# Reverse_current.net
KiCad netlist of a schematic drawn in EAGLE
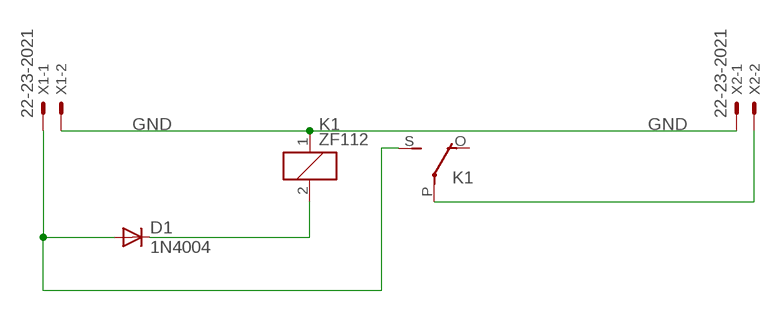
[diagram p0: schematic, sheet 1]

(export (version "E")
  (design (tool "Eeschema 10.0.6"))
  (components
    (comp (ref "D1")
      (value "1N4004")
      (footprint "eagle-import:DO41-10")
      (libsource (lib "eagle-import") (part "1N4004"))
    )
    (comp (ref "K1")
      (value "ZF112")
      (footprint "eagle-import:ZF112")
      (libsource (lib "eagle-import") (part "ZF112"))
    )
    (comp (ref "X1")
      (value "22-23-2021")
      (footprint "eagle-import:22-23-2021")
      (fields (field (name "MF") "MOLEX"))
      (libsource (lib "eagle-import") (part "22-23-2021"))
    )
    (comp (ref "X2")
      (value "22-23-2021")
      (footprint "eagle-import:22-23-2021")
      (fields (field (name "MF") "MOLEX"))
      (libsource (lib "eagle-import") (part "22-23-2021"))
    )
  )
  (nets
    (net (code "1") (name "/GND") (class "Default")
      (node (ref "K1") (pin "1") (pinfunction "1_1") (pintype "passive"))
      (node (ref "X1") (pin "2") (pinfunction "S_2") (pintype "passive"))
      (node (ref "X2") (pin "1") (pinfunction "S_1") (pintype "passive"))
    )
    (net (code "2") (name "Net-(D1-PadC)") (class "Default")
      (node (ref "D1") (pin "C") (pinfunction "C_C") (pintype "passive"))
      (node (ref "K1") (pin "2") (pinfunction "2_2") (pintype "passive"))
    )
    (net (code "3") (name "Net-(X1A-S)") (class "Default")
      (node (ref "D1") (pin "A") (pinfunction "A_A") (pintype "passive"))
      (node (ref "K1") (pin "S") (pinfunction "S_S") (pintype "passive"))
      (node (ref "X1") (pin "1") (pinfunction "S_1") (pintype "passive"))
    )
    (net (code "4") (name "Net-(X2B-S)") (class "Default")
      (node (ref "K1") (pin "P") (pinfunction "P_P") (pintype "passive"))
      (node (ref "X2") (pin "2") (pinfunction "S_2") (pintype "passive"))
    )
    (net (code "5") (name "unconnected-(K1-PadO)") (class "Default")
      (node (ref "K1") (pin "O") (pinfunction "O_O") (pintype "passive"))
    )
  )
)
